# MoteinoM0_mic_v0_2.net
KiCad netlist of a schematic drawn in EAGLE
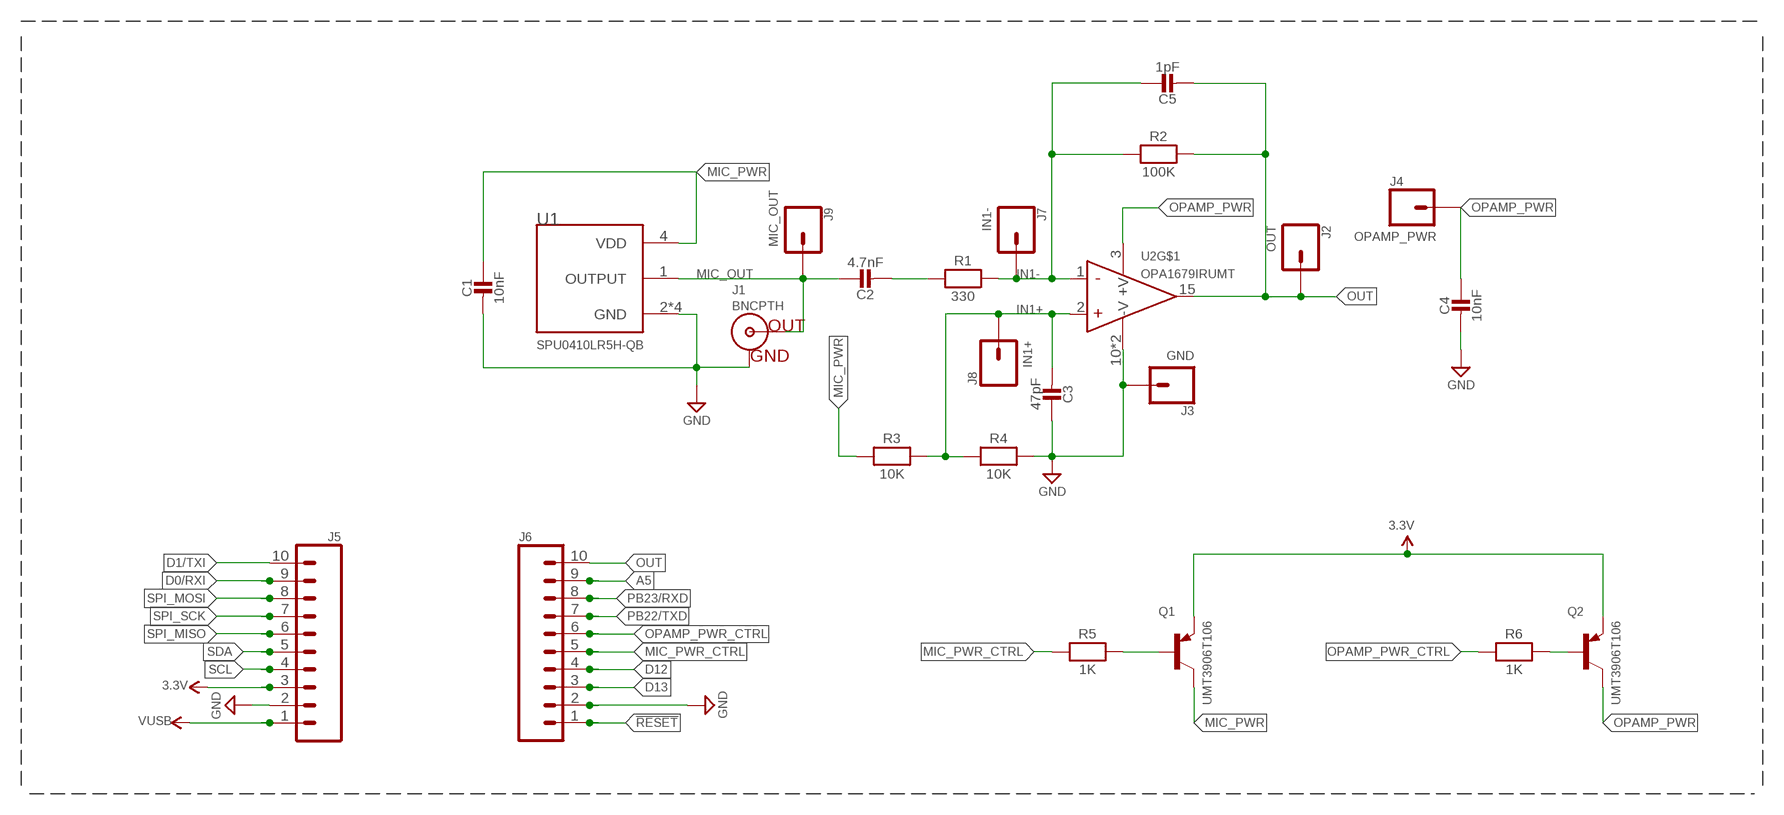
[diagram p0: schematic, sheet 1]

(export (version "E")
  (design (tool "Eeschema 10.0.6"))
  (components
    (comp (ref "C1")
      (value "10nF")
      (footprint "eagle-import:MICROBUILDER__0402MP")
      (fields (field (name "MPN") "GRM155R71H104KE14J"))
      (libsource (lib "eagle-import") (part "MICROBUILDER_CAP_CERAMIC_0402MP"))
    )
    (comp (ref "C2")
      (value "4.7nF")
      (footprint "eagle-import:MICROBUILDER__0402MP")
      (fields (field (name "MPN") "GRM155R71H104KE14J"))
      (libsource (lib "eagle-import") (part "MICROBUILDER_CAP_CERAMIC_0402MP"))
    )
    (comp (ref "C3")
      (value "47pF")
      (footprint "eagle-import:MICROBUILDER__0402MP")
      (fields (field (name "MPN") "GRM155R71H104KE14J"))
      (libsource (lib "eagle-import") (part "MICROBUILDER_CAP_CERAMIC_0402MP"))
    )
    (comp (ref "C4")
      (value "10nF")
      (footprint "eagle-import:MICROBUILDER__0402MP")
      (fields (field (name "MPN") "GRM155R71H104KE14J"))
      (libsource (lib "eagle-import") (part "MICROBUILDER_CAP_CERAMIC_0402MP"))
    )
    (comp (ref "C5")
      (value "1pF")
      (footprint "eagle-import:MICROBUILDER__0402MP")
      (fields (field (name "MPN") "GRM155R71H104KE14J"))
      (libsource (lib "eagle-import") (part "MICROBUILDER_CAP_CERAMIC_0402MP"))
    )
    (comp (ref "J1")
      (value "BNCPTH")
      (footprint "eagle-import:BNC")
      (libsource (lib "eagle-import") (part "BNCPTH"))
    )
    (comp (ref "J2")
      (value "OUT")
      (footprint "eagle-import:1X01")
      (libsource (lib "eagle-import") (part "CONN_01"))
    )
    (comp (ref "J3")
      (value "GND")
      (footprint "eagle-import:1X01")
      (libsource (lib "eagle-import") (part "CONN_01"))
    )
    (comp (ref "J4")
      (value "OPAMP_PWR")
      (footprint "eagle-import:1X01")
      (libsource (lib "eagle-import") (part "CONN_01"))
    )
    (comp (ref "J5")
      (value "CONN_10NO_SILK_PTH_FEMALE")
      (footprint "eagle-import:1X10_NO_SILK")
      (libsource (lib "eagle-import") (part "CONN_10NO_SILK_PTH_FEMALE"))
    )
    (comp (ref "J6")
      (value "CONN_10NO_SILK_PTH_FEMALE")
      (footprint "eagle-import:1X10_NO_SILK")
      (libsource (lib "eagle-import") (part "CONN_10NO_SILK_PTH_FEMALE"))
    )
    (comp (ref "J7")
      (value "IN1-")
      (footprint "eagle-import:1X01")
      (libsource (lib "eagle-import") (part "CONN_01"))
    )
    (comp (ref "J8")
      (value "IN1+")
      (footprint "eagle-import:1X01")
      (libsource (lib "eagle-import") (part "CONN_01"))
    )
    (comp (ref "J9")
      (value "MIC_OUT")
      (footprint "eagle-import:1X01")
      (libsource (lib "eagle-import") (part "CONN_01"))
    )
    (comp (ref "Q1")
      (value "UMT3906T106")
      (footprint "eagle-import:SOT65P210X100-3N-PNP")
      (libsource (lib "eagle-import") (part "UMT3906T106"))
    )
    (comp (ref "Q2")
      (value "UMT3906T106")
      (footprint "eagle-import:SOT65P210X100-3N-PNP")
      (libsource (lib "eagle-import") (part "UMT3906T106"))
    )
    (comp (ref "R1")
      (value "330")
      (footprint "eagle-import:MICROBUILDER__0402MP")
      (fields (field (name "MPN") "RC0402FR-074K7P"))
      (libsource (lib "eagle-import") (part "MICROBUILDER_RESISTOR_0402MP"))
    )
    (comp (ref "R2")
      (value "100K")
      (footprint "eagle-import:MICROBUILDER__0402MP")
      (fields (field (name "MPN") "RC0402FR-074K7P"))
      (libsource (lib "eagle-import") (part "MICROBUILDER_RESISTOR_0402MP"))
    )
    (comp (ref "R3")
      (value "10K")
      (footprint "eagle-import:MICROBUILDER__0402MP")
      (fields (field (name "MPN") "RC0402FR-074K7P"))
      (libsource (lib "eagle-import") (part "MICROBUILDER_RESISTOR_0402MP"))
    )
    (comp (ref "R4")
      (value "10K")
      (footprint "eagle-import:MICROBUILDER__0402MP")
      (fields (field (name "MPN") "RC0402FR-074K7P"))
      (libsource (lib "eagle-import") (part "MICROBUILDER_RESISTOR_0402MP"))
    )
    (comp (ref "R5")
      (value "1K")
      (footprint "eagle-import:MICROBUILDER__0402MP")
      (fields (field (name "MPN") "RC0402FR-074K7P"))
      (libsource (lib "eagle-import") (part "MICROBUILDER_RESISTOR_0402MP"))
    )
    (comp (ref "R6")
      (value "1K")
      (footprint "eagle-import:MICROBUILDER__0402MP")
      (fields (field (name "MPN") "RC0402FR-074K7P"))
      (libsource (lib "eagle-import") (part "MICROBUILDER_RESISTOR_0402MP"))
    )
    (comp (ref "U1")
      (value "SPU0410LR5H-QB")
      (footprint "eagle-import:XDCR_SPU0410LR5H-QB")
      (fields (field (name "MF") "Knowles"))
      (libsource (lib "eagle-import") (part "SPU0410LR5H-QB"))
    )
    (comp (ref "U2")
      (value "OPA1679IRUMT")
      (footprint "eagle-import:QFN65P400X400X80-17N")
      (libsource (lib "eagle-import") (part "OPA1679IRUMT"))
    )
  )
  (nets
    (net (code "1") (name "/IN1+") (class "Default")
      (node (ref "C3") (pin "2") (pinfunction "2_2") (pintype "passive"))
      (node (ref "J8") (pin "1") (pinfunction "1_1") (pintype "passive"))
      (node (ref "R3") (pin "2") (pinfunction "2_2") (pintype "passive"))
      (node (ref "R4") (pin "1") (pinfunction "1_1") (pintype "passive"))
      (node (ref "U2") (pin "2") (pinfunction "+IN_2") (pintype "input"))
    )
    (net (code "2") (name "/IN1-") (class "Default")
      (node (ref "C5") (pin "1") (pinfunction "1_1") (pintype "passive"))
      (node (ref "J7") (pin "1") (pinfunction "1_1") (pintype "passive"))
      (node (ref "R1") (pin "2") (pinfunction "2_2") (pintype "passive"))
      (node (ref "R2") (pin "1") (pinfunction "1_1") (pintype "passive"))
      (node (ref "U2") (pin "1") (pinfunction "-IN_1") (pintype "input"))
    )
    (net (code "3") (name "/MIC_OUT") (class "Default")
      (node (ref "C2") (pin "1") (pinfunction "1_1") (pintype "passive"))
      (node (ref "J1") (pin "S") (pinfunction "OUT_S") (pintype "bidirectional"))
      (node (ref "J9") (pin "1") (pinfunction "1_1") (pintype "passive"))
      (node (ref "U1") (pin "1") (pinfunction "OUTPUT_1") (pintype "output"))
    )
    (net (code "4") (name "/~{RESET}") (class "Default")
      (node (ref "J6") (pin "1") (pinfunction "1_1") (pintype "passive"))
    )
    (net (code "5") (name "3.3V") (class "Default")
      (node (ref "J5") (pin "3") (pinfunction "3_3") (pintype "passive"))
      (node (ref "Q1") (pin "1") (pinfunction "E_1") (pintype "passive"))
      (node (ref "Q2") (pin "1") (pinfunction "E_1") (pintype "passive"))
    )
    (net (code "6") (name "A5") (class "Default")
      (node (ref "J6") (pin "9") (pinfunction "9_9") (pintype "passive"))
    )
    (net (code "7") (name "D0{slash}RXI") (class "Default")
      (node (ref "J5") (pin "9") (pinfunction "9_9") (pintype "passive"))
    )
    (net (code "8") (name "D1{slash}TXI") (class "Default")
      (node (ref "J5") (pin "10") (pinfunction "10_10") (pintype "passive"))
    )
    (net (code "9") (name "D12") (class "Default")
      (node (ref "J6") (pin "4") (pinfunction "4_4") (pintype "passive"))
    )
    (net (code "10") (name "D13") (class "Default")
      (node (ref "J6") (pin "3") (pinfunction "3_3") (pintype "passive"))
    )
    (net (code "11") (name "GND") (class "Default")
      (node (ref "C1") (pin "2") (pinfunction "2_2") (pintype "passive"))
      (node (ref "C3") (pin "1") (pinfunction "1_1") (pintype "passive"))
      (node (ref "C4") (pin "2") (pinfunction "2_2") (pintype "passive"))
      (node (ref "J1") (pin "GND") (pinfunction "GND_GND") (pintype "bidirectional"))
      (node (ref "J3") (pin "1") (pinfunction "1_1") (pintype "passive"))
      (node (ref "J5") (pin "2") (pinfunction "2_2") (pintype "passive"))
      (node (ref "J6") (pin "2") (pinfunction "2_2") (pintype "passive"))
      (node (ref "R4") (pin "2") (pinfunction "2_2") (pintype "passive"))
      (node (ref "U1") (pin "2") (pinfunction "GND_2") (pintype "power_in"))
      (node (ref "U1") (pin "3") (pinfunction "GND_3") (pintype "power_in"))
      (node (ref "U1") (pin "5") (pinfunction "GND_5") (pintype "power_in"))
      (node (ref "U1") (pin "6") (pinfunction "GND_6") (pintype "power_in"))
      (node (ref "U2") (pin "10") (pinfunction "-V_10") (pintype "power_in"))
      (node (ref "U2") (pin "17") (pinfunction "-V_17") (pintype "power_in"))
    )
    (net (code "12") (name "MIC_PWR") (class "Default")
      (node (ref "C1") (pin "1") (pinfunction "1_1") (pintype "passive"))
      (node (ref "Q1") (pin "3") (pinfunction "C_3") (pintype "passive"))
      (node (ref "R3") (pin "1") (pinfunction "1_1") (pintype "passive"))
      (node (ref "U1") (pin "4") (pinfunction "VDD_4") (pintype "power_in"))
    )
    (net (code "13") (name "MIC_PWR_CTRL") (class "Default")
      (node (ref "J6") (pin "5") (pinfunction "5_5") (pintype "passive"))
      (node (ref "R5") (pin "1") (pinfunction "1_1") (pintype "passive"))
    )
    (net (code "14") (name "Net-(C2-Pad2)") (class "Default")
      (node (ref "C2") (pin "2") (pinfunction "2_2") (pintype "passive"))
      (node (ref "R1") (pin "1") (pinfunction "1_1") (pintype "passive"))
    )
    (net (code "15") (name "Net-(Q1-B)") (class "Default")
      (node (ref "Q1") (pin "2") (pinfunction "B_2") (pintype "passive"))
      (node (ref "R5") (pin "2") (pinfunction "2_2") (pintype "passive"))
    )
    (net (code "16") (name "Net-(Q2-B)") (class "Default")
      (node (ref "Q2") (pin "2") (pinfunction "B_2") (pintype "passive"))
      (node (ref "R6") (pin "2") (pinfunction "2_2") (pintype "passive"))
    )
    (net (code "17") (name "OPAMP_PWR") (class "Default")
      (node (ref "C4") (pin "1") (pinfunction "1_1") (pintype "passive"))
      (node (ref "J4") (pin "1") (pinfunction "1_1") (pintype "passive"))
      (node (ref "Q2") (pin "3") (pinfunction "C_3") (pintype "passive"))
      (node (ref "U2") (pin "3") (pinfunction "+V_3") (pintype "power_in"))
    )
    (net (code "18") (name "OPAMP_PWR_CTRL") (class "Default")
      (node (ref "J6") (pin "6") (pinfunction "6_6") (pintype "passive"))
      (node (ref "R6") (pin "1") (pinfunction "1_1") (pintype "passive"))
    )
    (net (code "19") (name "OUT") (class "Default")
      (node (ref "C5") (pin "2") (pinfunction "2_2") (pintype "passive"))
      (node (ref "J2") (pin "1") (pinfunction "1_1") (pintype "passive"))
      (node (ref "J6") (pin "10") (pinfunction "10_10") (pintype "passive"))
      (node (ref "R2") (pin "2") (pinfunction "2_2") (pintype "passive"))
      (node (ref "U2") (pin "15") (pinfunction "OUT_15") (pintype "output"))
    )
    (net (code "20") (name "PB22{slash}TXD") (class "Default")
      (node (ref "J6") (pin "7") (pinfunction "7_7") (pintype "passive"))
    )
    (net (code "21") (name "PB23{slash}RXD") (class "Default")
      (node (ref "J6") (pin "8") (pinfunction "8_8") (pintype "passive"))
    )
    (net (code "22") (name "SCL") (class "Default")
      (node (ref "J5") (pin "4") (pinfunction "4_4") (pintype "passive"))
    )
    (net (code "23") (name "SDA") (class "Default")
      (node (ref "J5") (pin "5") (pinfunction "5_5") (pintype "passive"))
    )
    (net (code "24") (name "SPI_MISO") (class "Default")
      (node (ref "J5") (pin "6") (pinfunction "6_6") (pintype "passive"))
    )
    (net (code "25") (name "SPI_MOSI") (class "Default")
      (node (ref "J5") (pin "8") (pinfunction "8_8") (pintype "passive"))
    )
    (net (code "26") (name "SPI_SCK") (class "Default")
      (node (ref "J5") (pin "7") (pinfunction "7_7") (pintype "passive"))
    )
    (net (code "27") (name "VUSB") (class "Default")
      (node (ref "J5") (pin "1") (pinfunction "1_1") (pintype "passive"))
    )
  )
)
